# VU_meter.net
KiCad netlist of a schematic drawn in EAGLE
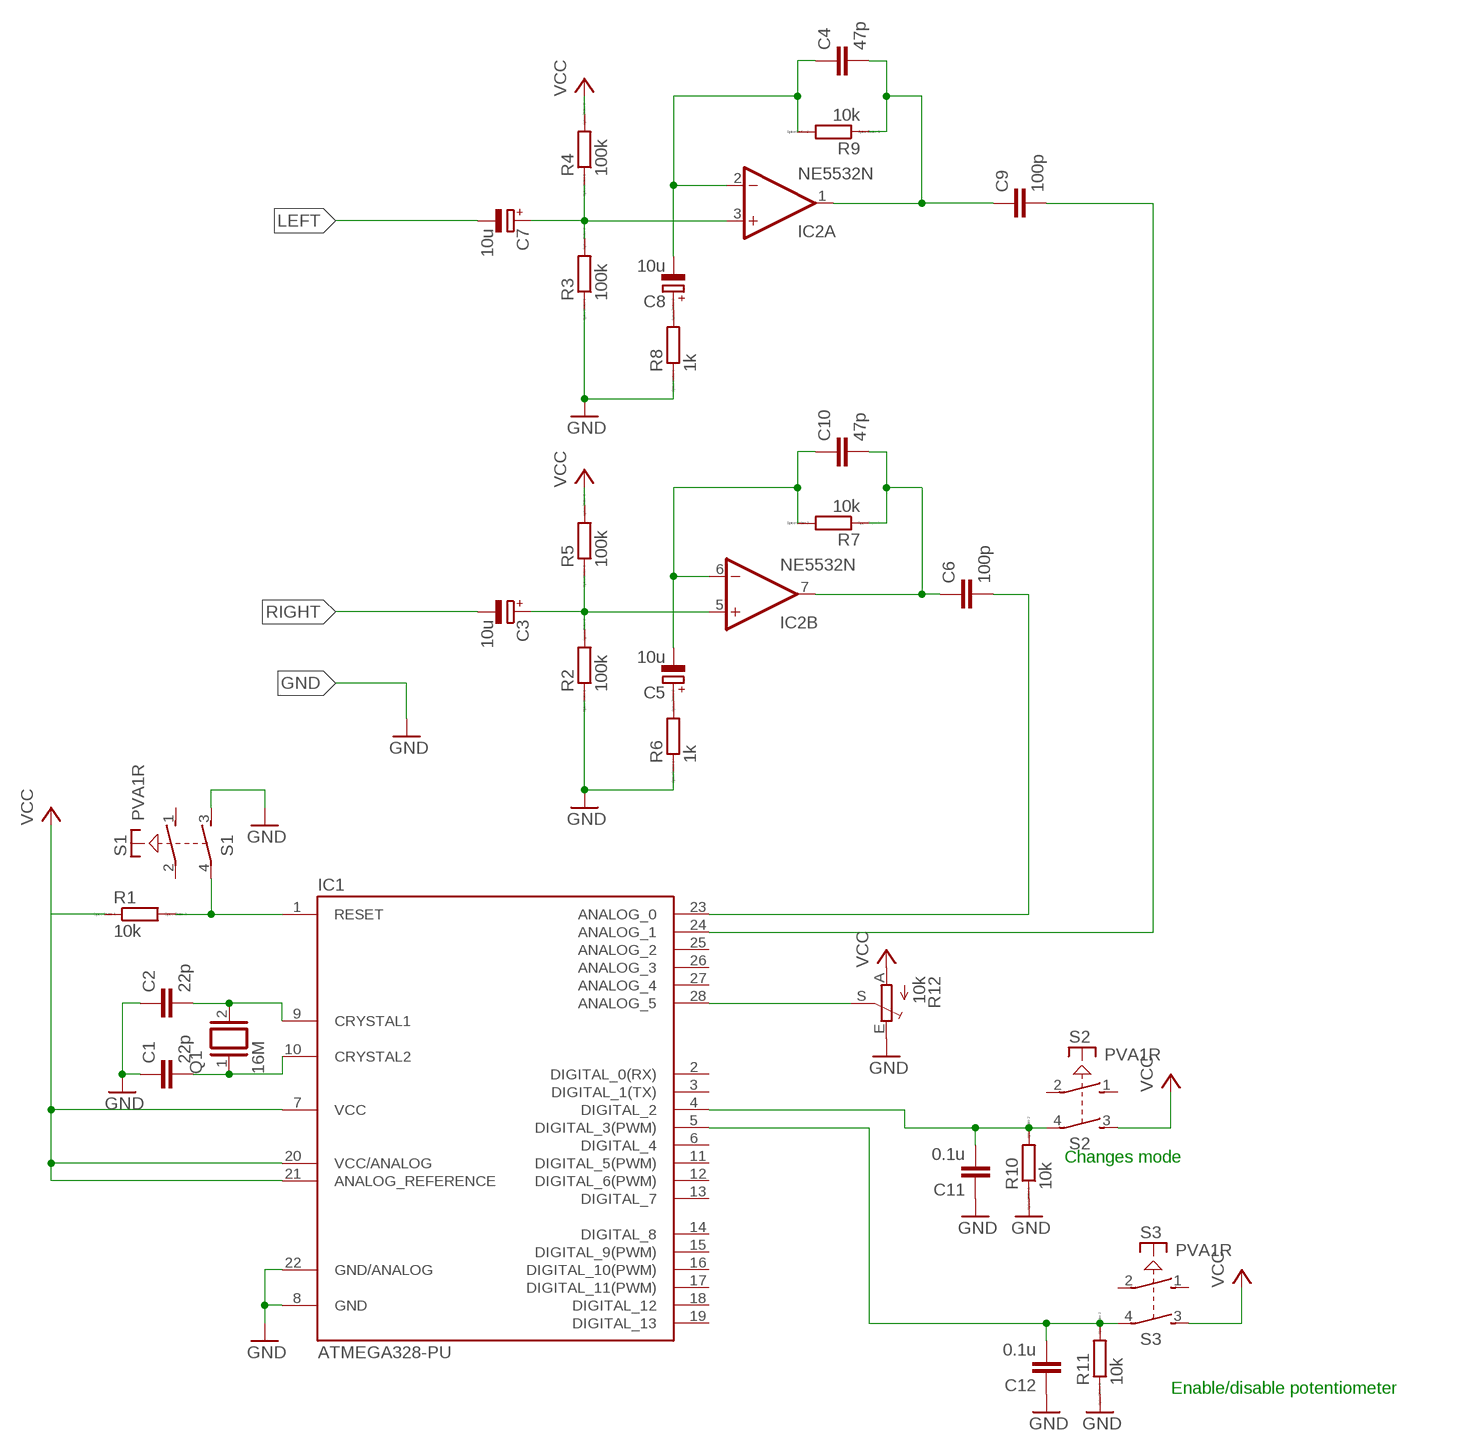
[diagram p0: schematic, sheet 1]

(export (version "E")
  (design (tool "Eeschema 10.0.6"))
  (components
    (comp (ref "C1")
      (value "22p")
      (footprint "eagle-import:C5B5")
      (libsource (lib "eagle-import") (part "C5/5"))
    )
    (comp (ref "C2")
      (value "22p")
      (footprint "eagle-import:C5B5")
      (libsource (lib "eagle-import") (part "C5/5"))
    )
    (comp (ref "C3")
      (value "10u")
      (footprint "eagle-import:E2-5")
      (libsource (lib "eagle-import") (part "CPOL-EUE2-5"))
    )
    (comp (ref "C4")
      (value "47p")
      (footprint "eagle-import:C5B5")
      (libsource (lib "eagle-import") (part "C5/5"))
    )
    (comp (ref "C5")
      (value "10u")
      (footprint "eagle-import:E2-5")
      (libsource (lib "eagle-import") (part "CPOL-EUE2-5"))
    )
    (comp (ref "C6")
      (value "100p")
      (footprint "eagle-import:C5B5")
      (libsource (lib "eagle-import") (part "C5/5"))
    )
    (comp (ref "C7")
      (value "10u")
      (footprint "eagle-import:E2-5")
      (libsource (lib "eagle-import") (part "CPOL-EUE2-5"))
    )
    (comp (ref "C8")
      (value "10u")
      (footprint "eagle-import:E2-5")
      (libsource (lib "eagle-import") (part "CPOL-EUE2-5"))
    )
    (comp (ref "C9")
      (value "100p")
      (footprint "eagle-import:C5B5")
      (libsource (lib "eagle-import") (part "C5/5"))
    )
    (comp (ref "C10")
      (value "47p")
      (footprint "eagle-import:C5B5")
      (libsource (lib "eagle-import") (part "C5/5"))
    )
    (comp (ref "C11")
      (value "0.1u")
      (footprint "eagle-import:C5B5")
      (libsource (lib "eagle-import") (part "C5/5"))
    )
    (comp (ref "C12")
      (value "0.1u")
      (footprint "eagle-import:C5B5")
      (libsource (lib "eagle-import") (part "C5/5"))
    )
    (comp (ref "IC1")
      (value "ATMEGA328-PU")
      (footprint "eagle-import:DIL28-3")
      (libsource (lib "eagle-import") (part "ATMEGA168-PU"))
    )
    (comp (ref "IC2")
      (value "NE5532N")
      (footprint "eagle-import:DIL08")
      (libsource (lib "eagle-import") (part "NE5532N"))
    )
    (comp (ref "Q1")
      (value "16M")
      (footprint "eagle-import:QS")
      (libsource (lib "eagle-import") (part "XTAL/S"))
    )
    (comp (ref "R1")
      (value "10k")
      (footprint "eagle-import:0207_10")
      (libsource (lib "eagle-import") (part "R0207/10"))
    )
    (comp (ref "R2")
      (value "100k")
      (footprint "eagle-import:0207_10")
      (libsource (lib "eagle-import") (part "R0207/10"))
    )
    (comp (ref "R3")
      (value "100k")
      (footprint "eagle-import:0207_10")
      (libsource (lib "eagle-import") (part "R0207/10"))
    )
    (comp (ref "R4")
      (value "100k")
      (footprint "eagle-import:0207_10")
      (libsource (lib "eagle-import") (part "R0207/10"))
    )
    (comp (ref "R5")
      (value "100k")
      (footprint "eagle-import:0207_10")
      (libsource (lib "eagle-import") (part "R0207/10"))
    )
    (comp (ref "R6")
      (value "1k")
      (footprint "eagle-import:0207_10")
      (libsource (lib "eagle-import") (part "R0207/10"))
    )
    (comp (ref "R7")
      (value "10k")
      (footprint "eagle-import:0207_10")
      (libsource (lib "eagle-import") (part "R0207/10"))
    )
    (comp (ref "R8")
      (value "1k")
      (footprint "eagle-import:0207_10")
      (libsource (lib "eagle-import") (part "R0207/10"))
    )
    (comp (ref "R9")
      (value "10k")
      (footprint "eagle-import:0207_10")
      (libsource (lib "eagle-import") (part "R0207/10"))
    )
    (comp (ref "R10")
      (value "10k")
      (footprint "eagle-import:0207_10")
      (libsource (lib "eagle-import") (part "R0207/10"))
    )
    (comp (ref "R11")
      (value "10k")
      (footprint "eagle-import:0207_10")
      (libsource (lib "eagle-import") (part "R0207/10"))
    )
    (comp (ref "R12")
      (value "10k")
      (footprint "eagle-import:CIP20C-6MM")
      (libsource (lib "eagle-import") (part "TRIM_EU-CIP20C-6MM"))
    )
    (comp (ref "S1")
      (value "PVA1R")
      (footprint "eagle-import:PVA1R")
      (libsource (lib "eagle-import") (part "PVA1R"))
    )
    (comp (ref "S2")
      (value "PVA1R")
      (footprint "eagle-import:PVA1R")
      (libsource (lib "eagle-import") (part "PVA1R"))
    )
    (comp (ref "S3")
      (value "PVA1R")
      (footprint "eagle-import:PVA1R")
      (libsource (lib "eagle-import") (part "PVA1R"))
    )
  )
  (nets
    (net (code "1") (name "GND") (class "Default")
      (node (ref "C1") (pin "1") (pinfunction "1_1") (pintype "passive"))
      (node (ref "C11") (pin "1") (pinfunction "1_1") (pintype "passive"))
      (node (ref "C12") (pin "1") (pinfunction "1_1") (pintype "passive"))
      (node (ref "C2") (pin "1") (pinfunction "1_1") (pintype "passive"))
      (node (ref "IC1") (pin "22") (pinfunction "GND/ANALOG_22") (pintype "power_in"))
      (node (ref "IC1") (pin "8") (pinfunction "GND_8") (pintype "power_in"))
      (node (ref "R10") (pin "1") (pinfunction "1_1") (pintype "passive"))
      (node (ref "R11") (pin "1") (pinfunction "1_1") (pintype "passive"))
      (node (ref "R12") (pin "E") (pinfunction "E_E") (pintype "passive"))
      (node (ref "R2") (pin "1") (pinfunction "1_1") (pintype "passive"))
      (node (ref "R3") (pin "1") (pinfunction "1_1") (pintype "passive"))
      (node (ref "R6") (pin "1") (pinfunction "1_1") (pintype "passive"))
      (node (ref "R8") (pin "1") (pinfunction "1_1") (pintype "passive"))
      (node (ref "S1") (pin "3") (pinfunction "S_3") (pintype "passive"))
    )
    (net (code "2") (name "LEFT") (class "Default")
      (node (ref "C7") (pin "-") (pinfunction "-_-") (pintype "passive"))
    )
    (net (code "3") (name "Net-(C5-Pad+)") (class "Default")
      (node (ref "C5") (pin "+") (pinfunction "+_+") (pintype "passive"))
      (node (ref "R6") (pin "2") (pinfunction "2_2") (pintype "passive"))
    )
    (net (code "4") (name "Net-(C8-Pad+)") (class "Default")
      (node (ref "C8") (pin "+") (pinfunction "+_+") (pintype "passive"))
      (node (ref "R8") (pin "2") (pinfunction "2_2") (pintype "passive"))
    )
    (net (code "5") (name "Net-(IC1-ANALOG_0)") (class "Default")
      (node (ref "C6") (pin "2") (pinfunction "2_2") (pintype "passive"))
      (node (ref "IC1") (pin "23") (pinfunction "ANALOG_0_23") (pintype "bidirectional"))
    )
    (net (code "6") (name "Net-(IC1-ANALOG_1)") (class "Default")
      (node (ref "C9") (pin "2") (pinfunction "2_2") (pintype "passive"))
      (node (ref "IC1") (pin "24") (pinfunction "ANALOG_1_24") (pintype "bidirectional"))
    )
    (net (code "7") (name "Net-(IC1-ANALOG_5)") (class "Default")
      (node (ref "IC1") (pin "28") (pinfunction "ANALOG_5_28") (pintype "bidirectional"))
      (node (ref "R12") (pin "S") (pinfunction "S_S") (pintype "passive"))
    )
    (net (code "8") (name "Net-(IC1-CRYSTAL1)") (class "Default")
      (node (ref "C2") (pin "2") (pinfunction "2_2") (pintype "passive"))
      (node (ref "IC1") (pin "9") (pinfunction "CRYSTAL1_9") (pintype "bidirectional"))
      (node (ref "Q1") (pin "2") (pinfunction "2_2") (pintype "passive"))
    )
    (net (code "9") (name "Net-(IC1-CRYSTAL2)") (class "Default")
      (node (ref "C1") (pin "2") (pinfunction "2_2") (pintype "passive"))
      (node (ref "IC1") (pin "10") (pinfunction "CRYSTAL2_10") (pintype "bidirectional"))
      (node (ref "Q1") (pin "1") (pinfunction "1_1") (pintype "passive"))
    )
    (net (code "10") (name "Net-(IC1-DIGITAL_2)") (class "Default")
      (node (ref "C11") (pin "2") (pinfunction "2_2") (pintype "passive"))
      (node (ref "IC1") (pin "4") (pinfunction "DIGITAL_2_4") (pintype "bidirectional"))
      (node (ref "R10") (pin "2") (pinfunction "2_2") (pintype "passive"))
      (node (ref "S2") (pin "4") (pinfunction "P_4") (pintype "passive"))
    )
    (net (code "11") (name "Net-(IC1-DIGITAL_3(PWM))") (class "Default")
      (node (ref "C12") (pin "2") (pinfunction "2_2") (pintype "passive"))
      (node (ref "IC1") (pin "5") (pinfunction "DIGITAL_3(PWM)_5") (pintype "bidirectional"))
      (node (ref "R11") (pin "2") (pinfunction "2_2") (pintype "passive"))
      (node (ref "S3") (pin "4") (pinfunction "P_4") (pintype "passive"))
    )
    (net (code "12") (name "Net-(IC1-RESET)") (class "Default")
      (node (ref "IC1") (pin "1") (pinfunction "RESET_1") (pintype "bidirectional"))
      (node (ref "R1") (pin "2") (pinfunction "2_2") (pintype "passive"))
      (node (ref "S1") (pin "4") (pinfunction "P_4") (pintype "passive"))
    )
    (net (code "13") (name "Net-(IC2A-+IN)") (class "Default")
      (node (ref "C7") (pin "+") (pinfunction "+_+") (pintype "passive"))
      (node (ref "IC2") (pin "3") (pinfunction "+IN_3") (pintype "input"))
      (node (ref "R3") (pin "2") (pinfunction "2_2") (pintype "passive"))
      (node (ref "R4") (pin "1") (pinfunction "1_1") (pintype "passive"))
    )
    (net (code "14") (name "Net-(IC2A--IN)") (class "Default")
      (node (ref "C4") (pin "1") (pinfunction "1_1") (pintype "passive"))
      (node (ref "C8") (pin "-") (pinfunction "-_-") (pintype "passive"))
      (node (ref "IC2") (pin "2") (pinfunction "-IN_2") (pintype "input"))
      (node (ref "R9") (pin "2") (pinfunction "2_2") (pintype "passive"))
    )
    (net (code "15") (name "Net-(IC2A-OUT)") (class "Default")
      (node (ref "C4") (pin "2") (pinfunction "2_2") (pintype "passive"))
      (node (ref "C9") (pin "1") (pinfunction "1_1") (pintype "passive"))
      (node (ref "IC2") (pin "1") (pinfunction "OUT_1") (pintype "output"))
      (node (ref "R9") (pin "1") (pinfunction "1_1") (pintype "passive"))
    )
    (net (code "16") (name "Net-(IC2B-+IN)") (class "Default")
      (node (ref "C3") (pin "+") (pinfunction "+_+") (pintype "passive"))
      (node (ref "IC2") (pin "5") (pinfunction "+IN_5") (pintype "input"))
      (node (ref "R2") (pin "2") (pinfunction "2_2") (pintype "passive"))
      (node (ref "R5") (pin "1") (pinfunction "1_1") (pintype "passive"))
    )
    (net (code "17") (name "Net-(IC2B--IN)") (class "Default")
      (node (ref "C10") (pin "1") (pinfunction "1_1") (pintype "passive"))
      (node (ref "C5") (pin "-") (pinfunction "-_-") (pintype "passive"))
      (node (ref "IC2") (pin "6") (pinfunction "-IN_6") (pintype "input"))
      (node (ref "R7") (pin "2") (pinfunction "2_2") (pintype "passive"))
    )
    (net (code "18") (name "Net-(IC2B-OUT)") (class "Default")
      (node (ref "C10") (pin "2") (pinfunction "2_2") (pintype "passive"))
      (node (ref "C6") (pin "1") (pinfunction "1_1") (pintype "passive"))
      (node (ref "IC2") (pin "7") (pinfunction "OUT_7") (pintype "output"))
      (node (ref "R7") (pin "1") (pinfunction "1_1") (pintype "passive"))
    )
    (net (code "19") (name "RIGHT") (class "Default")
      (node (ref "C3") (pin "-") (pinfunction "-_-") (pintype "passive"))
    )
    (net (code "20") (name "VCC") (class "Default")
      (node (ref "IC1") (pin "20") (pinfunction "VCC/ANALOG_20") (pintype "passive"))
      (node (ref "IC1") (pin "21") (pinfunction "ANALOG_REFERENCE_21") (pintype "passive"))
      (node (ref "IC1") (pin "7") (pinfunction "VCC_7") (pintype "power_in"))
      (node (ref "R1") (pin "1") (pinfunction "1_1") (pintype "passive"))
      (node (ref "R12") (pin "A") (pinfunction "A_A") (pintype "passive"))
      (node (ref "R4") (pin "2") (pinfunction "2_2") (pintype "passive"))
      (node (ref "R5") (pin "2") (pinfunction "2_2") (pintype "passive"))
      (node (ref "S2") (pin "3") (pinfunction "S_3") (pintype "passive"))
      (node (ref "S3") (pin "3") (pinfunction "S_3") (pintype "passive"))
    )
    (net (code "21") (name "unconnected-(IC1-ANALOG_2-Pad25)") (class "Default")
      (node (ref "IC1") (pin "25") (pinfunction "ANALOG_2_25") (pintype "bidirectional"))
    )
    (net (code "22") (name "unconnected-(IC1-ANALOG_3-Pad26)") (class "Default")
      (node (ref "IC1") (pin "26") (pinfunction "ANALOG_3_26") (pintype "bidirectional"))
    )
    (net (code "23") (name "unconnected-(IC1-ANALOG_4-Pad27)") (class "Default")
      (node (ref "IC1") (pin "27") (pinfunction "ANALOG_4_27") (pintype "bidirectional"))
    )
    (net (code "24") (name "unconnected-(IC1-DIGITAL_0(RX)-Pad2)") (class "Default")
      (node (ref "IC1") (pin "2") (pinfunction "DIGITAL_0(RX)_2") (pintype "bidirectional"))
    )
    (net (code "25") (name "unconnected-(IC1-DIGITAL_1(TX)-Pad3)") (class "Default")
      (node (ref "IC1") (pin "3") (pinfunction "DIGITAL_1(TX)_3") (pintype "bidirectional"))
    )
    (net (code "26") (name "unconnected-(IC1-DIGITAL_4-Pad6)") (class "Default")
      (node (ref "IC1") (pin "6") (pinfunction "DIGITAL_4_6") (pintype "bidirectional"))
    )
    (net (code "27") (name "unconnected-(IC1-DIGITAL_5(PWM)-Pad11)") (class "Default")
      (node (ref "IC1") (pin "11") (pinfunction "DIGITAL_5(PWM)_11") (pintype "bidirectional"))
    )
    (net (code "28") (name "unconnected-(IC1-DIGITAL_6(PWM)-Pad12)") (class "Default")
      (node (ref "IC1") (pin "12") (pinfunction "DIGITAL_6(PWM)_12") (pintype "bidirectional"))
    )
    (net (code "29") (name "unconnected-(IC1-DIGITAL_7-Pad13)") (class "Default")
      (node (ref "IC1") (pin "13") (pinfunction "DIGITAL_7_13") (pintype "bidirectional"))
    )
    (net (code "30") (name "unconnected-(IC1-DIGITAL_8-Pad14)") (class "Default")
      (node (ref "IC1") (pin "14") (pinfunction "DIGITAL_8_14") (pintype "bidirectional"))
    )
    (net (code "31") (name "unconnected-(IC1-DIGITAL_9(PWM)-Pad15)") (class "Default")
      (node (ref "IC1") (pin "15") (pinfunction "DIGITAL_9(PWM)_15") (pintype "bidirectional"))
    )
    (net (code "32") (name "unconnected-(IC1-DIGITAL_10(PWM)-Pad16)") (class "Default")
      (node (ref "IC1") (pin "16") (pinfunction "DIGITAL_10(PWM)_16") (pintype "bidirectional"))
    )
    (net (code "33") (name "unconnected-(IC1-DIGITAL_11(PWM)-Pad17)") (class "Default")
      (node (ref "IC1") (pin "17") (pinfunction "DIGITAL_11(PWM)_17") (pintype "bidirectional"))
    )
    (net (code "34") (name "unconnected-(IC1-DIGITAL_12-Pad18)") (class "Default")
      (node (ref "IC1") (pin "18") (pinfunction "DIGITAL_12_18") (pintype "bidirectional"))
    )
    (net (code "35") (name "unconnected-(IC1-DIGITAL_13-Pad19)") (class "Default")
      (node (ref "IC1") (pin "19") (pinfunction "DIGITAL_13_19") (pintype "bidirectional"))
    )
    (net (code "36") (name "unconnected-(S1A-P-Pad2)") (class "Default")
      (node (ref "S1") (pin "2") (pinfunction "P_2") (pintype "passive"))
    )
    (net (code "37") (name "unconnected-(S1A-S-Pad1)") (class "Default")
      (node (ref "S1") (pin "1") (pinfunction "S_1") (pintype "passive"))
    )
    (net (code "38") (name "unconnected-(S2A-P-Pad2)") (class "Default")
      (node (ref "S2") (pin "2") (pinfunction "P_2") (pintype "passive"))
    )
    (net (code "39") (name "unconnected-(S2A-S-Pad1)") (class "Default")
      (node (ref "S2") (pin "1") (pinfunction "S_1") (pintype "passive"))
    )
    (net (code "40") (name "unconnected-(S3A-P-Pad2)") (class "Default")
      (node (ref "S3") (pin "2") (pinfunction "P_2") (pintype "passive"))
    )
    (net (code "41") (name "unconnected-(S3A-S-Pad1)") (class "Default")
      (node (ref "S3") (pin "1") (pinfunction "S_1") (pintype "passive"))
    )
  )
)
